# 2_Microcontroller.net
KiCad netlist of a schematic drawn in Altium Designer
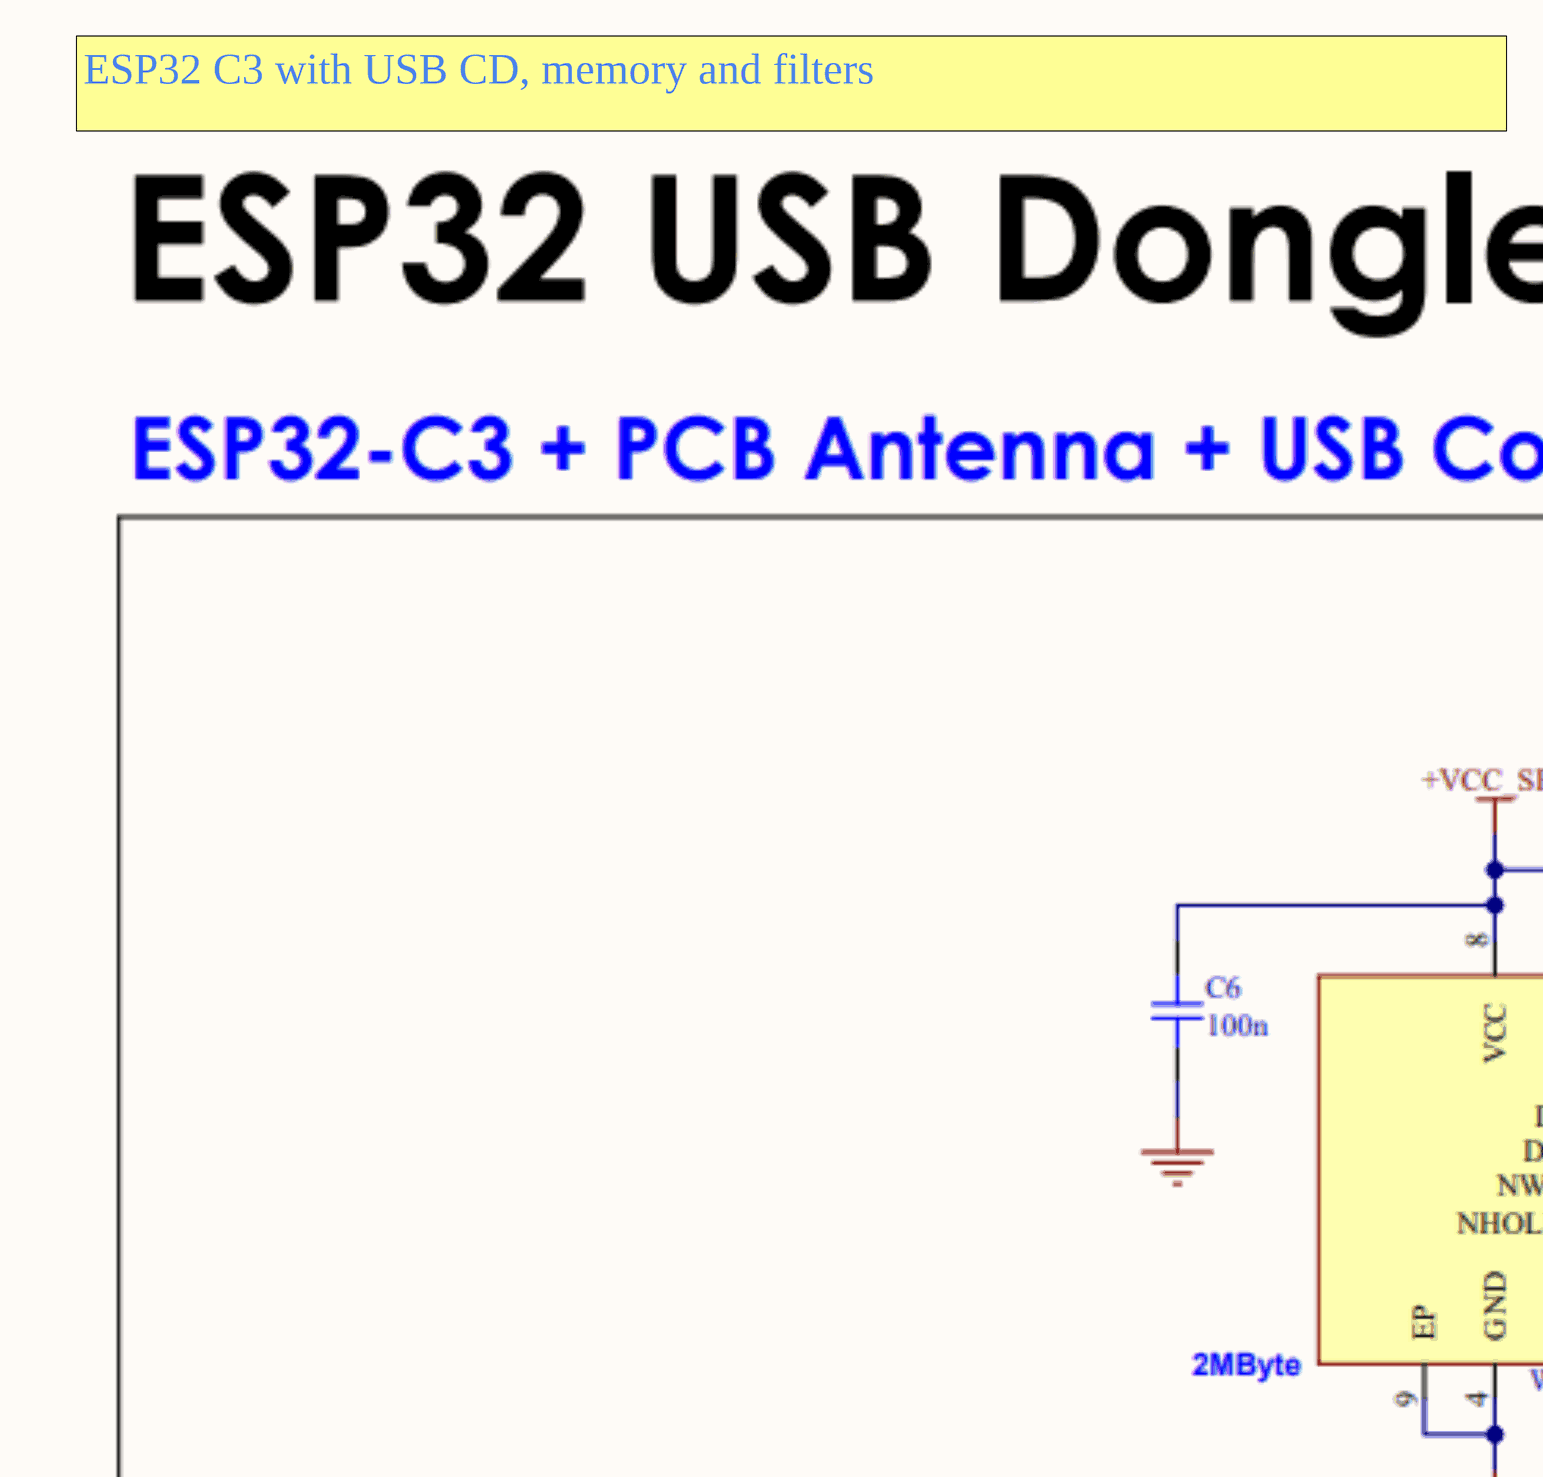
[diagram p0: 2_Microcontroller.SchDoc, top right]
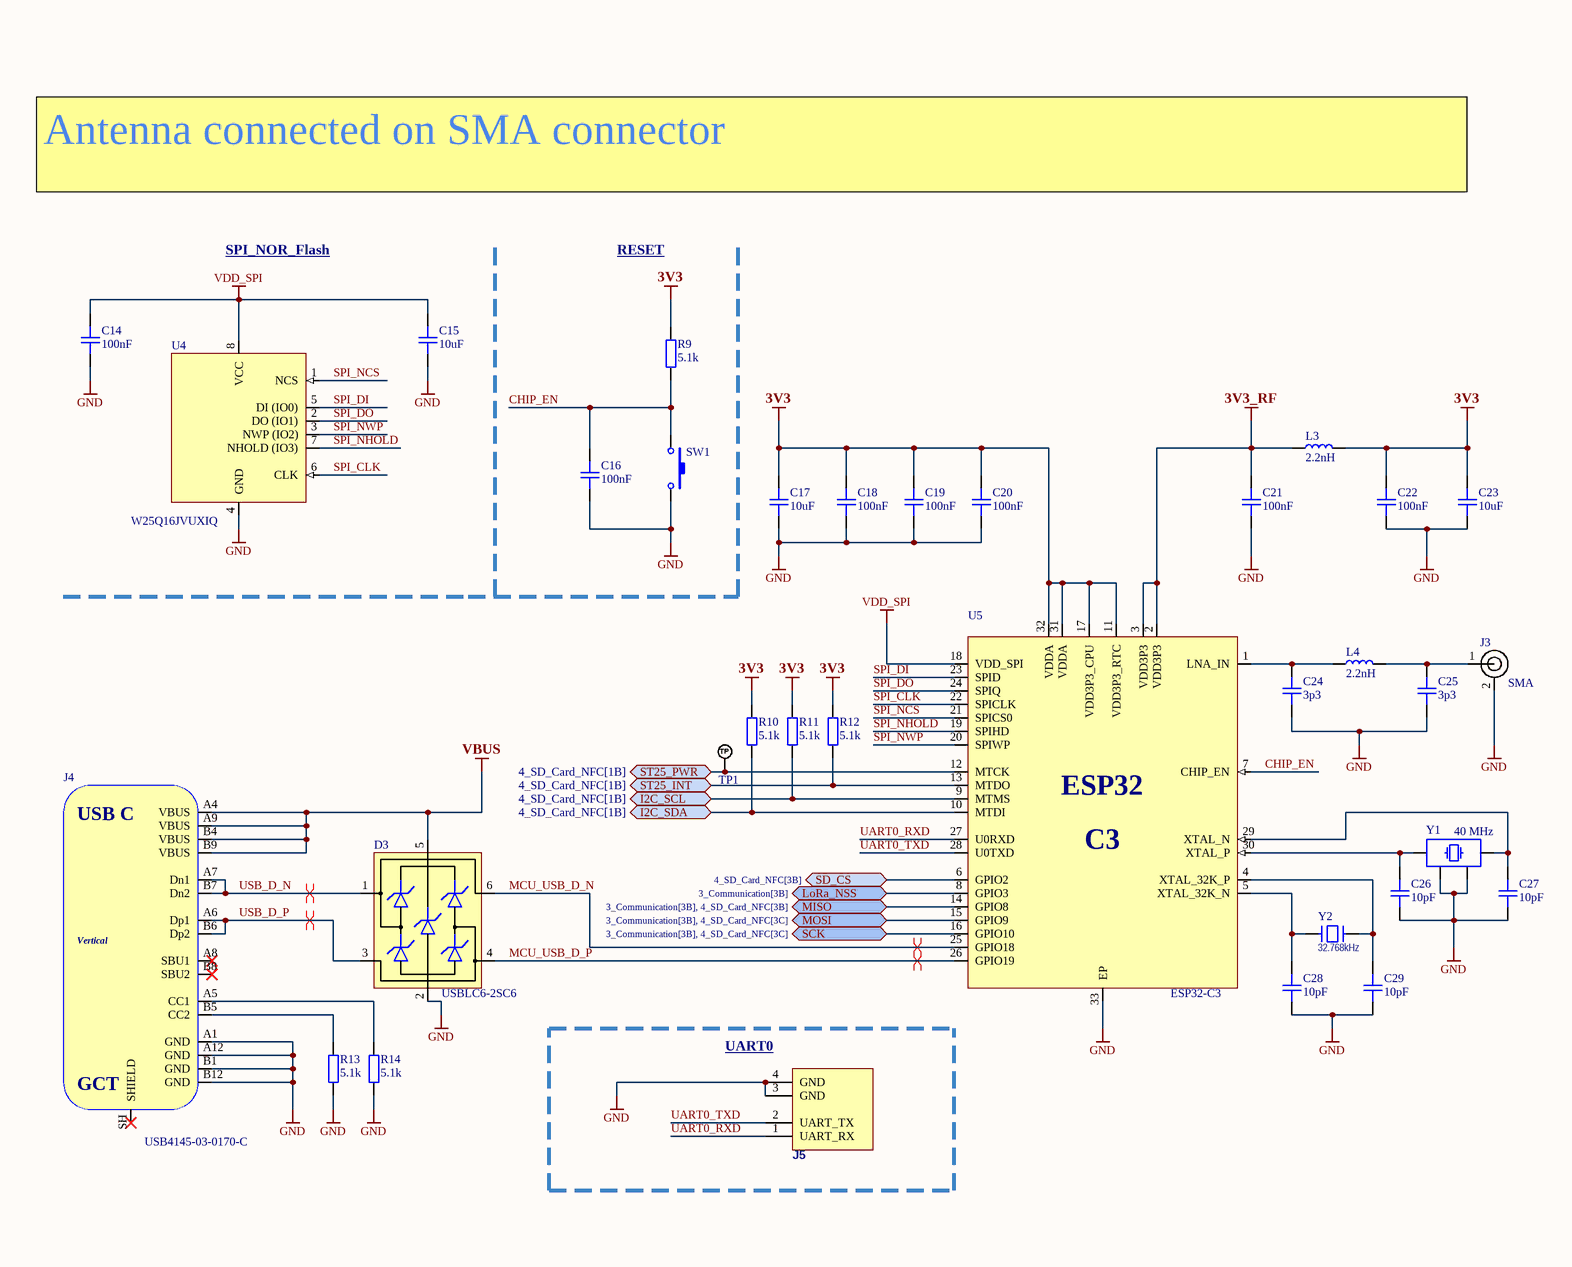
[diagram p1: 2_Microcontroller.SchDoc, bottom left]
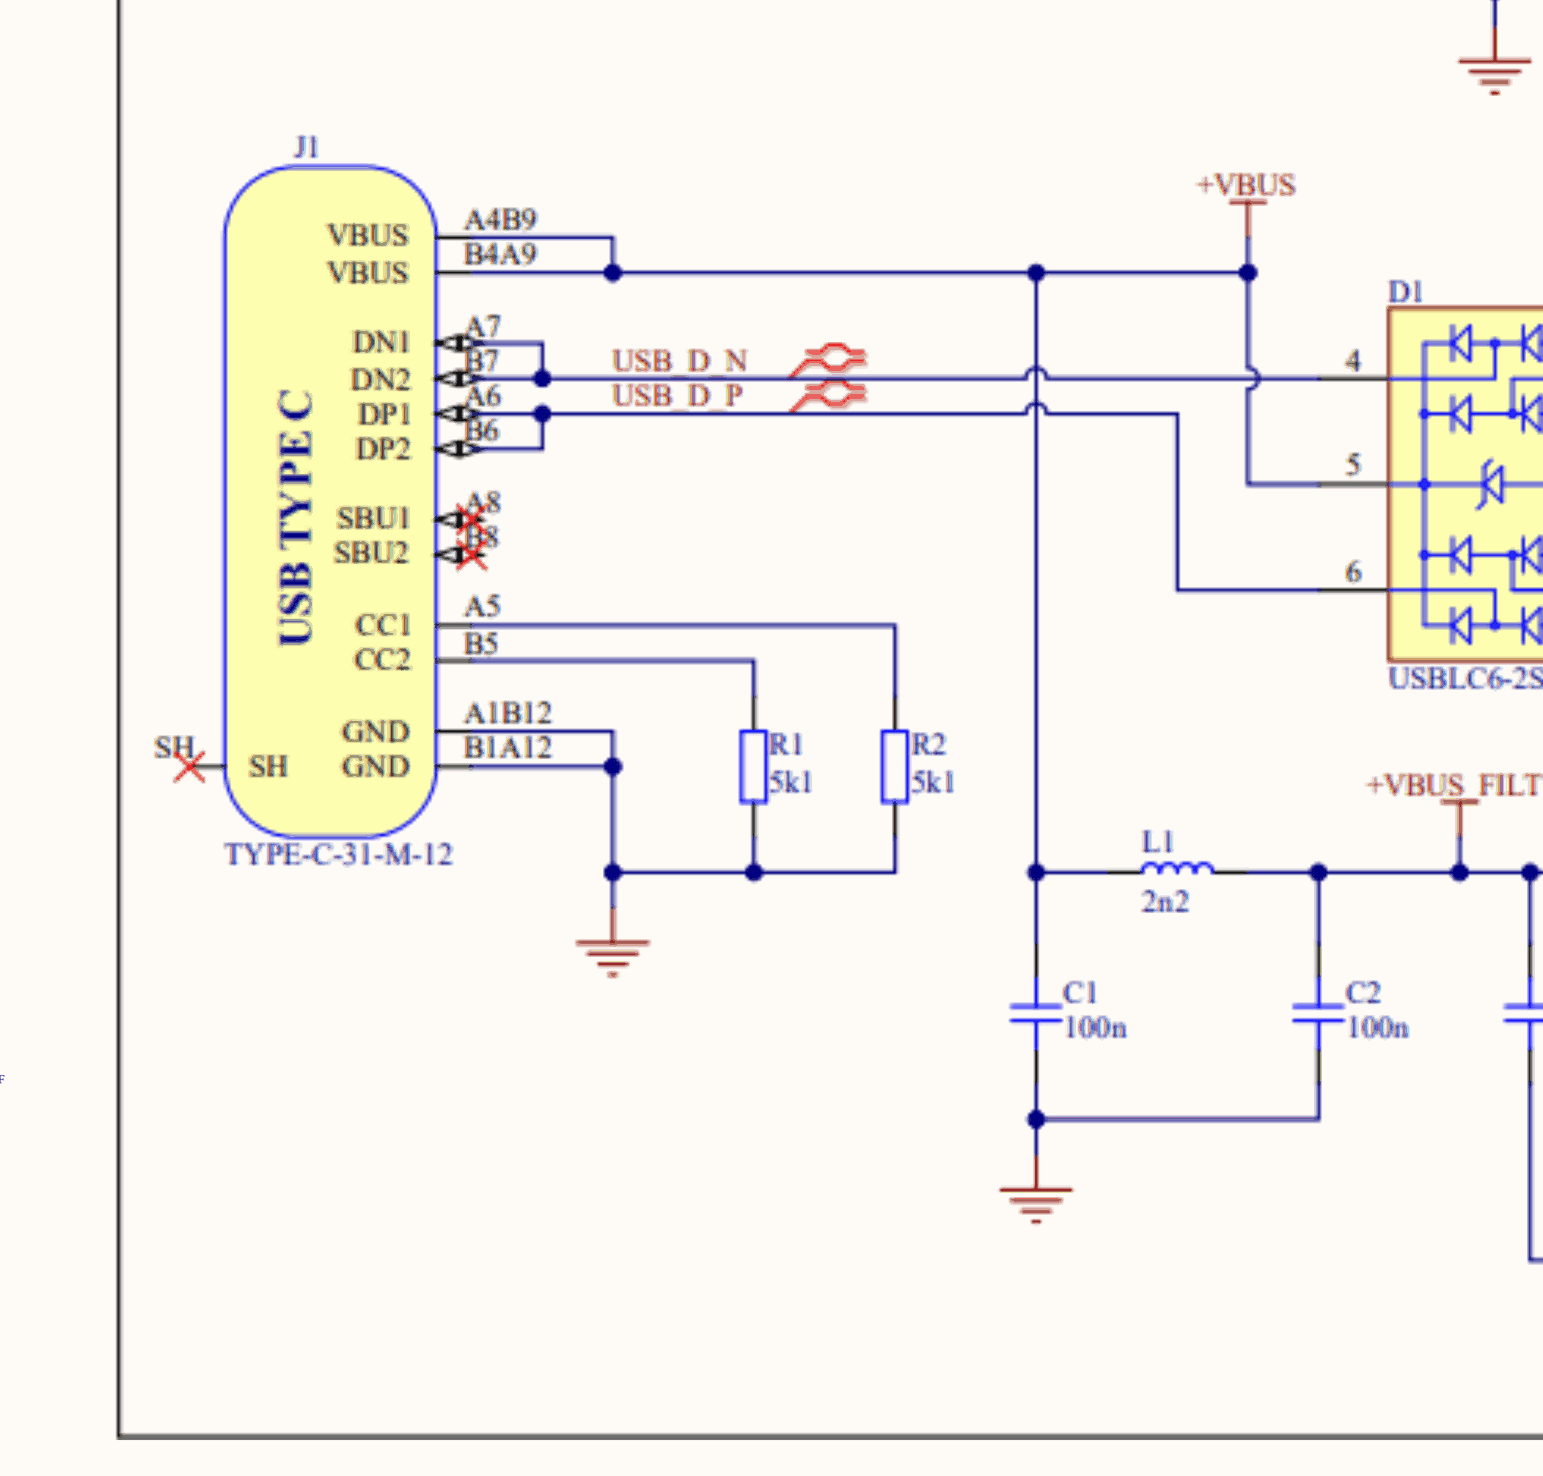
[diagram p2: 2_Microcontroller.SchDoc, bottom right]

(export (version "E")
  (design (tool "Eeschema 10.0.6"))
  (components
    (comp (ref "C14")
      (value "100nF")
      (footprint "C0603")
      (description "Capacitor SMD 0603")
      (libsource (lib "Schlib1") (part "CAP_0603"))
    )
    (comp (ref "C15")
      (value "10uF")
      (footprint "C0805")
      (description "Capacitor SMD 0805")
      (libsource (lib "Schlib1") (part "CAP_0805"))
    )
    (comp (ref "C16")
      (value "100nF")
      (footprint "C0603")
      (description "Capacitor SMD 0603")
      (libsource (lib "Schlib1") (part "CAP_0603"))
    )
    (comp (ref "C17")
      (value "10uF")
      (footprint "C0805")
      (description "Capacitor SMD 0805")
      (libsource (lib "Schlib1") (part "CAP_0805"))
    )
    (comp (ref "C18")
      (value "100nF")
      (footprint "C0603")
      (description "Capacitor SMD 0603")
      (libsource (lib "Schlib1") (part "CAP_0603"))
    )
    (comp (ref "C19")
      (value "100nF")
      (footprint "C0603")
      (description "Capacitor SMD 0603")
      (libsource (lib "Schlib1") (part "CAP_0603"))
    )
    (comp (ref "C20")
      (value "100nF")
      (footprint "C0603")
      (description "Capacitor SMD 0603")
      (libsource (lib "Schlib1") (part "CAP_0603"))
    )
    (comp (ref "C21")
      (value "100nF")
      (footprint "C0603")
      (description "Capacitor SMD 0603")
      (libsource (lib "Schlib1") (part "CAP_0603"))
    )
    (comp (ref "C22")
      (value "100nF")
      (footprint "C0603")
      (description "Capacitor SMD 0603")
      (libsource (lib "Schlib1") (part "CAP_0603"))
    )
    (comp (ref "C23")
      (value "10uF")
      (footprint "C0805")
      (description "Capacitor SMD 0805")
      (libsource (lib "Schlib1") (part "CAP_0805"))
    )
    (comp (ref "C24")
      (value "3p3")
      (footprint "C0603")
      (description "Capacitor SMD 0603")
      (libsource (lib "Schlib1") (part "CAP_0603"))
    )
    (comp (ref "C25")
      (value "3p3")
      (footprint "C0603")
      (description "Capacitor SMD 0603")
      (libsource (lib "Schlib1") (part "CAP_0603"))
    )
    (comp (ref "C26")
      (value "10pF")
      (footprint "C0603")
      (description "Capacitor SMD 0603")
      (libsource (lib "Schlib1") (part "CAP_0603"))
    )
    (comp (ref "C27")
      (value "10pF")
      (footprint "C0603")
      (description "Capacitor SMD 0603")
      (libsource (lib "Schlib1") (part "CAP_0603"))
    )
    (comp (ref "C28")
      (value "10pF")
      (footprint "C0603")
      (description "Capacitor SMD 0603")
      (libsource (lib "Schlib1") (part "CAP_0603"))
    )
    (comp (ref "C29")
      (value "10pF")
      (footprint "C0603")
      (description "Capacitor SMD 0603")
      (libsource (lib "Schlib1") (part "CAP_0603"))
    )
    (comp (ref "D3")
      (value "USBLC6-2SC6")
      (footprint "SOT23-6")
      (description "Low-Capacitance ESD Protection USB")
      (fields (field (name "MANUFACTURER") "STMicroelectronics"))
      (libsource (lib "Schlib1") (part "USBLC6-2SC6"))
    )
    (comp (ref "J3")
      (value "SMA")
      (footprint "CON_SMA-EDGE-S")
      (description "RF Connector SMA Female 50 Ohms 18 GHz PCB Edge Mount")
      (fields
        (field (name "MANUFACTURER") "RF Solutions")
        (field (name "MANUFACTURER PART NUMBER") "CON-SMA-EDGE-S")
      )
      (libsource (lib "Schlib1") (part "CON-SMA-EDGE-S"))
    )
    (comp (ref "J4")
      (value "USB4145-03-0170-C")
      (footprint "VALCON_CSP-USC16-TR")
      (description "USB Connector Type C SMT 16 Pin Vertical")
      (fields (field (name "MANUFACTURER") "GCT"))
      (libsource (lib "Schlib1") (part "USB4145-03-0170-C"))
    )
    (comp (ref "J5")
      (value "Header1x4")
      (footprint "HEADER_2x2_2.54")
      (libsource (lib "Schlib1") (part "Header1x4"))
    )
    (comp (ref "L3")
      (value "2.2nH")
      (footprint "L0603")
      (description "Inductor SMD 1008")
      (libsource (lib "Schlib1") (part "IND_1008"))
    )
    (comp (ref "L4")
      (value "2.2nH")
      (footprint "L0603")
      (description "Inductor SMD 1008")
      (libsource (lib "Schlib1") (part "IND_1008"))
    )
    (comp (ref "R9")
      (value "5.1k")
      (footprint "R0603")
      (description "Resistor SMD 0603")
      (libsource (lib "Schlib1") (part "RES_0603"))
    )
    (comp (ref "R10")
      (value "5.1k")
      (footprint "R0603")
      (description "Resistor SMD 0603")
      (libsource (lib "Schlib1") (part "RES_0603"))
    )
    (comp (ref "R11")
      (value "5.1k")
      (footprint "R0603")
      (description "Resistor SMD 0603")
      (libsource (lib "Schlib1") (part "RES_0603"))
    )
    (comp (ref "R12")
      (value "5.1k")
      (footprint "R0603")
      (description "Resistor SMD 0603")
      (libsource (lib "Schlib1") (part "RES_0603"))
    )
    (comp (ref "R13")
      (value "5.1k")
      (footprint "R0603")
      (description "Resistor SMD 0603")
      (libsource (lib "Schlib1") (part "RES_0603"))
    )
    (comp (ref "R14")
      (value "5.1k")
      (footprint "R0603")
      (description "Resistor SMD 0603")
      (libsource (lib "Schlib1") (part "RES_0603"))
    )
    (comp (ref "SW1")
      (value "PTS645SM43SMTR92 LFS")
      (footprint "SW_SKRPACE010")
      (description "Switch")
      (fields (field (name "PUBLISHER") "Altium Limited"))
      (libsource (lib "Schlib1") (part "SW-PB"))
    )
    (comp (ref "TP1")
      (value "TP_NOBOM")
      (footprint "TEST_PAD_THD")
      (description "Test Point Round 1mm (NO BOM)")
      (libsource (lib "Schlib1") (part "TEST_POINT_RND_1MM"))
    )
    (comp (ref "U4")
      (value "W25Q16JVUXIQ")
      (footprint "SOIC-SN8_N")
      (description "16M-BIT SERIAL FLASH MEMORY WITH DUAL/QUAD SPI USON-8")
      (fields (field (name "MANUFACTURER") "Winbond"))
      (libsource (lib "Schlib1") (part "W25Q16JVUXIQ"))
    )
    (comp (ref "U5")
      (value "ESP32-C3")
      (footprint "QFN-32-5x5x0.85mm")
      (fields (field (name "MANUFACTURER") "Espressif"))
      (libsource (lib "Schlib1") (part "ESP32-C3"))
    )
    (comp (ref "Y1")
      (value "40 MHz")
      (footprint "CRYSTAL_ECX-32_3.2x2.5x0.8 - duplicate")
      (description "Crystal SMD 4-Pin 3225x4")
      (libsource (lib "Schlib1") (part "XTAL_2016"))
    )
    (comp (ref "Y2")
      (value "32.768kHz")
      (footprint "CRYSTAL_SX-3215")
      (description "Crystal")
      (libsource (lib "Schlib1") (part "CRYSTAL_1"))
    )
  )
  (nets
    (net (code "1") (name "/CHIP_EN") (class "Default")
      (node (ref "C16") (pin "2") (pinfunction "2_2") (pintype "passive"))
      (node (ref "R9") (pin "1") (pinfunction "1_1") (pintype "passive"))
      (node (ref "SW1") (pin "1") (pinfunction "1_1") (pintype "passive"))
      (node (ref "U5") (pin "7") (pinfunction "CHIP_EN_7") (pintype "input"))
    )
    (net (code "2") (name "/I2C_SCL") (class "Default")
      (node (ref "R11") (pin "1") (pinfunction "1_1") (pintype "passive"))
      (node (ref "U5") (pin "9") (pinfunction "MTMS_9") (pintype "bidirectional"))
    )
    (net (code "3") (name "/I2C_SDA") (class "Default")
      (node (ref "R10") (pin "1") (pinfunction "1_1") (pintype "passive"))
      (node (ref "U5") (pin "10") (pinfunction "MTDI_10") (pintype "bidirectional"))
    )
    (net (code "4") (name "/LoRa_NSS") (class "Default")
      (node (ref "U5") (pin "8") (pinfunction "GPIO3_8") (pintype "bidirectional"))
    )
    (net (code "5") (name "/MCU_USB_D_N") (class "Default")
      (node (ref "D3") (pin "6") (pinfunction "IO1_6") (pintype "passive"))
      (node (ref "U5") (pin "25") (pinfunction "GPIO18_25") (pintype "passive"))
    )
    (net (code "6") (name "/MCU_USB_D_P") (class "Default")
      (node (ref "D3") (pin "4") (pinfunction "IO2_4") (pintype "passive"))
      (node (ref "U5") (pin "26") (pinfunction "GPIO19_26") (pintype "passive"))
    )
    (net (code "7") (name "/MISO") (class "Default")
      (node (ref "U5") (pin "14") (pinfunction "GPIO8_14") (pintype "bidirectional"))
    )
    (net (code "8") (name "/MOSI") (class "Default")
      (node (ref "U5") (pin "15") (pinfunction "GPIO9_15") (pintype "bidirectional"))
    )
    (net (code "9") (name "/SCK") (class "Default")
      (node (ref "U5") (pin "16") (pinfunction "GPIO10_16") (pintype "bidirectional"))
    )
    (net (code "10") (name "/SD_CS") (class "Default")
      (node (ref "U5") (pin "6") (pinfunction "GPIO2_6") (pintype "bidirectional"))
    )
    (net (code "11") (name "/SPI_CLK") (class "Default")
      (node (ref "U4") (pin "6") (pinfunction "CLK_6") (pintype "input"))
      (node (ref "U5") (pin "22") (pinfunction "SPICLK_22") (pintype "bidirectional"))
    )
    (net (code "12") (name "/SPI_DI") (class "Default")
      (node (ref "U4") (pin "5") (pinfunction "DI_(IO0)_5") (pintype "bidirectional"))
      (node (ref "U5") (pin "23") (pinfunction "SPID_23") (pintype "bidirectional"))
    )
    (net (code "13") (name "/SPI_DO") (class "Default")
      (node (ref "U4") (pin "2") (pinfunction "DO_(IO1)_2") (pintype "bidirectional"))
      (node (ref "U5") (pin "24") (pinfunction "SPIQ_24") (pintype "bidirectional"))
    )
    (net (code "14") (name "/SPI_NCS") (class "Default")
      (node (ref "U4") (pin "1") (pinfunction "NCS_1") (pintype "input"))
      (node (ref "U5") (pin "21") (pinfunction "SPICS0_21") (pintype "bidirectional"))
    )
    (net (code "15") (name "/SPI_NHOLD") (class "Default")
      (node (ref "U4") (pin "7") (pinfunction "NHOLD_(IO3)_7") (pintype "bidirectional"))
      (node (ref "U5") (pin "19") (pinfunction "SPIHD_19") (pintype "bidirectional"))
    )
    (net (code "16") (name "/SPI_NWP") (class "Default")
      (node (ref "U4") (pin "3") (pinfunction "NWP_(IO2)_3") (pintype "bidirectional"))
      (node (ref "U5") (pin "20") (pinfunction "SPIWP_20") (pintype "bidirectional"))
    )
    (net (code "17") (name "/ST25_INT") (class "Default")
      (node (ref "R12") (pin "1") (pinfunction "1_1") (pintype "passive"))
      (node (ref "U5") (pin "13") (pinfunction "MTDO_13") (pintype "bidirectional"))
    )
    (net (code "18") (name "/ST25_PWR") (class "Default")
      (node (ref "TP1") (pin "1") (pinfunction "TP_1") (pintype "passive"))
      (node (ref "U5") (pin "12") (pinfunction "MTCK_12") (pintype "bidirectional"))
    )
    (net (code "19") (name "/UART0_RXD") (class "Default")
      (node (ref "J5") (pin "1") (pinfunction "UART_RX_1") (pintype "passive"))
      (node (ref "U5") (pin "27") (pinfunction "U0RXD_27") (pintype "bidirectional"))
    )
    (net (code "20") (name "/UART0_TXD") (class "Default")
      (node (ref "J5") (pin "2") (pinfunction "UART_TX_2") (pintype "passive"))
      (node (ref "U5") (pin "28") (pinfunction "U0TXD_28") (pintype "bidirectional"))
    )
    (net (code "21") (name "/USB_D_N") (class "Default")
      (node (ref "D3") (pin "1") (pinfunction "IO1_1") (pintype "passive"))
      (node (ref "J4") (pin "A7") (pinfunction "Dn1_A7") (pintype "passive"))
      (node (ref "J4") (pin "B7") (pinfunction "Dn2_B7") (pintype "passive"))
    )
    (net (code "22") (name "/USB_D_P") (class "Default")
      (node (ref "D3") (pin "3") (pinfunction "IO2_3") (pintype "passive"))
      (node (ref "J4") (pin "A6") (pinfunction "Dp1_A6") (pintype "passive"))
      (node (ref "J4") (pin "B6") (pinfunction "Dp2_B6") (pintype "passive"))
    )
    (net (code "23") (name "3V3") (class "Default")
      (node (ref "C17") (pin "2") (pinfunction "2_2") (pintype "passive"))
      (node (ref "C18") (pin "2") (pinfunction "2_2") (pintype "passive"))
      (node (ref "C19") (pin "2") (pinfunction "2_2") (pintype "passive"))
      (node (ref "C20") (pin "2") (pinfunction "2_2") (pintype "passive"))
      (node (ref "C22") (pin "2") (pinfunction "2_2") (pintype "passive"))
      (node (ref "C23") (pin "2") (pinfunction "2_2") (pintype "passive"))
      (node (ref "L3") (pin "2") (pinfunction "2_2") (pintype "passive"))
      (node (ref "R10") (pin "2") (pinfunction "2_2") (pintype "passive"))
      (node (ref "R11") (pin "2") (pinfunction "2_2") (pintype "passive"))
      (node (ref "R12") (pin "2") (pinfunction "2_2") (pintype "passive"))
      (node (ref "R9") (pin "2") (pinfunction "2_2") (pintype "passive"))
      (node (ref "U5") (pin "11") (pinfunction "VDD3P3_RTC_11") (pintype "power_in"))
      (node (ref "U5") (pin "17") (pinfunction "VDD3P3_CPU_17") (pintype "power_in"))
      (node (ref "U5") (pin "31") (pinfunction "VDDA_31") (pintype "power_in"))
      (node (ref "U5") (pin "32") (pinfunction "VDDA_32") (pintype "power_in"))
    )
    (net (code "24") (name "3V3_RF") (class "Default")
      (node (ref "C21") (pin "2") (pinfunction "2_2") (pintype "passive"))
      (node (ref "L3") (pin "1") (pinfunction "1_1") (pintype "passive"))
      (node (ref "U5") (pin "2") (pinfunction "VDD3P3_2") (pintype "power_in"))
      (node (ref "U5") (pin "3") (pinfunction "VDD3P3_3") (pintype "power_in"))
    )
    (net (code "25") (name "GND") (class "Default")
      (node (ref "C14") (pin "1") (pinfunction "1_1") (pintype "passive"))
      (node (ref "C15") (pin "1") (pinfunction "1_1") (pintype "passive"))
      (node (ref "C16") (pin "1") (pinfunction "1_1") (pintype "passive"))
      (node (ref "C17") (pin "1") (pinfunction "1_1") (pintype "passive"))
      (node (ref "C18") (pin "1") (pinfunction "1_1") (pintype "passive"))
      (node (ref "C19") (pin "1") (pinfunction "1_1") (pintype "passive"))
      (node (ref "C20") (pin "1") (pinfunction "1_1") (pintype "passive"))
      (node (ref "C21") (pin "1") (pinfunction "1_1") (pintype "passive"))
      (node (ref "C22") (pin "1") (pinfunction "1_1") (pintype "passive"))
      (node (ref "C23") (pin "1") (pinfunction "1_1") (pintype "passive"))
      (node (ref "C24") (pin "1") (pinfunction "1_1") (pintype "passive"))
      (node (ref "C25") (pin "1") (pinfunction "1_1") (pintype "passive"))
      (node (ref "C26") (pin "1") (pinfunction "1_1") (pintype "passive"))
      (node (ref "C27") (pin "1") (pinfunction "1_1") (pintype "passive"))
      (node (ref "C28") (pin "1") (pinfunction "1_1") (pintype "passive"))
      (node (ref "C29") (pin "1") (pinfunction "1_1") (pintype "passive"))
      (node (ref "D3") (pin "2") (pinfunction "GND_2") (pintype "power_in"))
      (node (ref "J3") (pin "2") (pinfunction "2_2") (pintype "passive"))
      (node (ref "J4") (pin "A1") (pinfunction "GND_A1") (pintype "passive"))
      (node (ref "J4") (pin "A12") (pinfunction "GND_A12") (pintype "passive"))
      (node (ref "J4") (pin "B1") (pinfunction "GND_B1") (pintype "passive"))
      (node (ref "J4") (pin "B12") (pinfunction "GND_B12") (pintype "passive"))
      (node (ref "J5") (pin "3") (pinfunction "GND_3") (pintype "passive"))
      (node (ref "J5") (pin "4") (pinfunction "GND_4") (pintype "passive"))
      (node (ref "R13") (pin "1") (pinfunction "1_1") (pintype "passive"))
      (node (ref "R14") (pin "1") (pinfunction "1_1") (pintype "passive"))
      (node (ref "SW1") (pin "2") (pinfunction "2_2") (pintype "passive"))
      (node (ref "U4") (pin "4") (pinfunction "GND_4") (pintype "power_in"))
      (node (ref "U5") (pin "33") (pinfunction "EP_33") (pintype "power_in"))
      (node (ref "Y1") (pin "2") (pinfunction "2_2") (pintype "passive"))
      (node (ref "Y1") (pin "4") (pinfunction "4_4") (pintype "passive"))
    )
    (net (code "26") (name "Net-(C25-Pad2)") (class "Default")
      (node (ref "C25") (pin "2") (pinfunction "2_2") (pintype "passive"))
      (node (ref "J3") (pin "1") (pinfunction "1_1") (pintype "passive"))
      (node (ref "L4") (pin "2") (pinfunction "2_2") (pintype "passive"))
    )
    (net (code "27") (name "Net-(J4-CC1)") (class "Default")
      (node (ref "J4") (pin "A5") (pinfunction "CC1_A5") (pintype "passive"))
      (node (ref "R14") (pin "2") (pinfunction "2_2") (pintype "passive"))
    )
    (net (code "28") (name "Net-(J4-CC2)") (class "Default")
      (node (ref "J4") (pin "B5") (pinfunction "CC2_B5") (pintype "passive"))
      (node (ref "R13") (pin "2") (pinfunction "2_2") (pintype "passive"))
    )
    (net (code "29") (name "Net-(U5-LNA_IN)") (class "Default")
      (node (ref "C24") (pin "2") (pinfunction "2_2") (pintype "passive"))
      (node (ref "L4") (pin "1") (pinfunction "1_1") (pintype "passive"))
      (node (ref "U5") (pin "1") (pinfunction "LNA_IN_1") (pintype "bidirectional"))
    )
    (net (code "30") (name "Net-(U5-XTAL_32K_N)") (class "Default")
      (node (ref "C28") (pin "2") (pinfunction "2_2") (pintype "passive"))
      (node (ref "U5") (pin "5") (pinfunction "XTAL_32K_N_5") (pintype "bidirectional"))
      (node (ref "Y2") (pin "2") (pinfunction "2_2") (pintype "passive"))
    )
    (net (code "31") (name "Net-(U5-XTAL_32K_P)") (class "Default")
      (node (ref "C29") (pin "2") (pinfunction "2_2") (pintype "passive"))
      (node (ref "U5") (pin "4") (pinfunction "XTAL_32K_P_4") (pintype "bidirectional"))
      (node (ref "Y2") (pin "1") (pinfunction "1_1") (pintype "passive"))
    )
    (net (code "32") (name "Net-(U5-XTAL_N)") (class "Default")
      (node (ref "C27") (pin "2") (pinfunction "2_2") (pintype "passive"))
      (node (ref "U5") (pin "29") (pinfunction "XTAL_N_29") (pintype "input"))
      (node (ref "Y1") (pin "3") (pinfunction "3_3") (pintype "passive"))
    )
    (net (code "33") (name "Net-(U5-XTAL_P)") (class "Default")
      (node (ref "C26") (pin "2") (pinfunction "2_2") (pintype "passive"))
      (node (ref "U5") (pin "30") (pinfunction "XTAL_P_30") (pintype "input"))
      (node (ref "Y1") (pin "1") (pinfunction "1_1") (pintype "passive"))
    )
    (net (code "34") (name "VBUS") (class "Default")
      (node (ref "D3") (pin "5") (pinfunction "VBUS_5") (pintype "power_in"))
      (node (ref "J4") (pin "A4") (pinfunction "VBUS_A4") (pintype "passive"))
      (node (ref "J4") (pin "A9") (pinfunction "VBUS_A9") (pintype "passive"))
      (node (ref "J4") (pin "B4") (pinfunction "VBUS_B4") (pintype "passive"))
      (node (ref "J4") (pin "B9") (pinfunction "VBUS_B9") (pintype "passive"))
    )
    (net (code "35") (name "VDD_SPI") (class "Default")
      (node (ref "C14") (pin "2") (pinfunction "2_2") (pintype "passive"))
      (node (ref "C15") (pin "2") (pinfunction "2_2") (pintype "passive"))
      (node (ref "U4") (pin "8") (pinfunction "VCC_8") (pintype "power_in"))
      (node (ref "U5") (pin "18") (pinfunction "VDD_SPI_18") (pintype "power_in"))
    )
    (net (code "36") (name "unconnected-(J4-SBU1-PadA8)") (class "Default")
      (node (ref "J4") (pin "A8") (pinfunction "SBU1_A8") (pintype "passive+no_connect"))
    )
    (net (code "37") (name "unconnected-(J4-SBU2-PadB8)") (class "Default")
      (node (ref "J4") (pin "B8") (pinfunction "SBU2_B8") (pintype "passive+no_connect"))
    )
    (net (code "38") (name "unconnected-(J4-SHIELD-PadSH)") (class "Default")
      (node (ref "J4") (pin "SH") (pinfunction "SHIELD_SH") (pintype "passive+no_connect"))
    )
  )
)
